# db9splitter.net
KiCad netlist of a schematic drawn in EAGLE
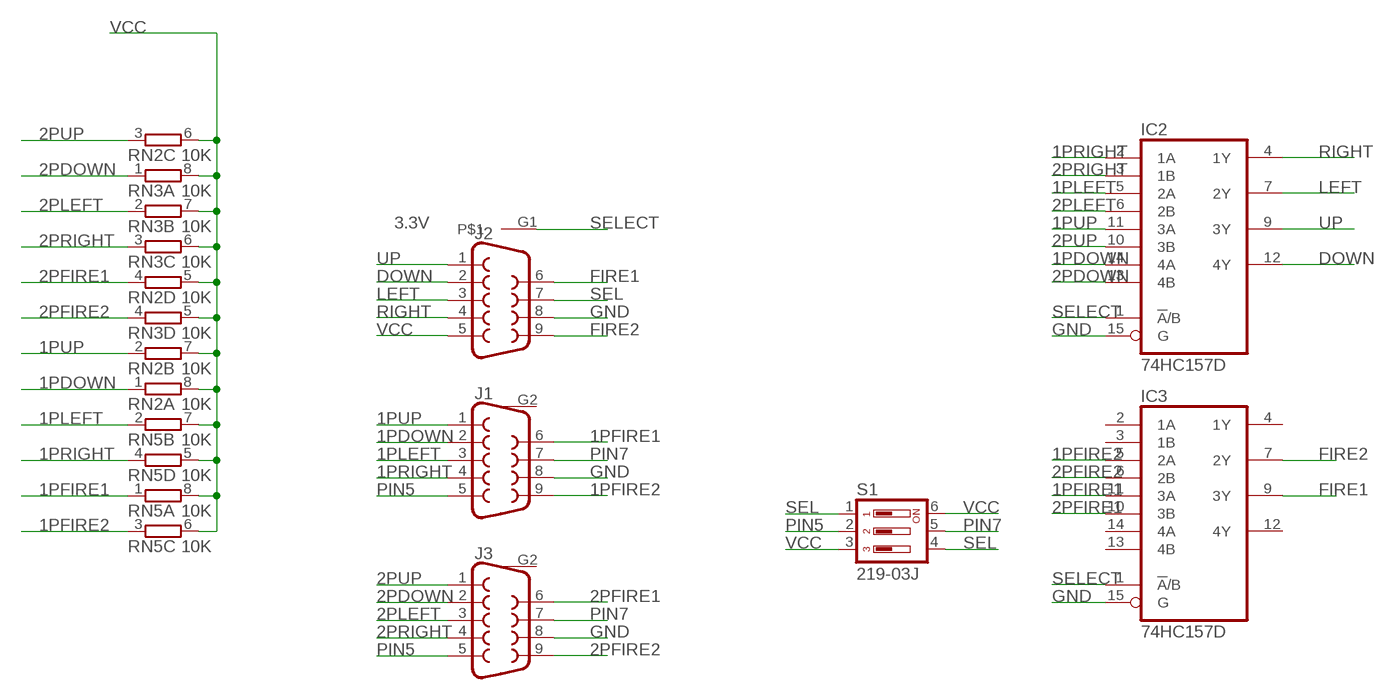
[diagram p0: schematic, sheet 1]

(export (version "E")
  (design (tool "Eeschema 10.0.6"))
  (components
    (comp (ref "IC2")
      (value "74HC157D")
      (footprint "eagle-import:SO16")
      (libsource (lib "eagle-import") (part "74157DHC"))
    )
    (comp (ref "IC3")
      (value "74HC157D")
      (footprint "eagle-import:SO16")
      (libsource (lib "eagle-import") (part "74157DHC"))
    )
    (comp (ref "J1")
      (value "SPARKFUN-CONNECTORS_DB9MALE")
      (footprint "eagle-import:SPARKFUN-CONNECTORS_DB9_MALE")
      (libsource (lib "eagle-import") (part "SPARKFUN-CONNECTORS_DB9MALE"))
    )
    (comp (ref "J2")
      (value "DB9FEMALE")
      (footprint "eagle-import:DB9")
      (libsource (lib "eagle-import") (part "DB9FEMALE"))
    )
    (comp (ref "J3")
      (value "SPARKFUN-CONNECTORS_DB9MALE")
      (footprint "eagle-import:SPARKFUN-CONNECTORS_DB9_MALE")
      (libsource (lib "eagle-import") (part "SPARKFUN-CONNECTORS_DB9MALE"))
    )
    (comp (ref "RN2")
      (value "10K")
      (footprint "eagle-import:0603-ARC")
      (libsource (lib "eagle-import") (part "4R-N0603-ARC"))
    )
    (comp (ref "RN3")
      (value "10K")
      (footprint "eagle-import:0603-ARC")
      (libsource (lib "eagle-import") (part "4R-N0603-ARC"))
    )
    (comp (ref "RN5")
      (value "10K")
      (footprint "eagle-import:0603-ARC")
      (libsource (lib "eagle-import") (part "4R-N0603-ARC"))
    )
    (comp (ref "S1")
      (value "219-03J")
      (footprint "eagle-import:CTS-219-03J")
      (libsource (lib "eagle-import") (part "219-03J"))
    )
  )
  (nets
    (net (code "1") (name "/1PDOWN") (class "Default")
      (node (ref "IC2") (pin "14") (pinfunction "4A_14") (pintype "input"))
      (node (ref "J1") (pin "2") (pinfunction "2_2") (pintype "passive"))
      (node (ref "RN2") (pin "1") (pinfunction "1_1") (pintype "passive"))
    )
    (net (code "2") (name "/1PFIRE1") (class "Default")
      (node (ref "IC3") (pin "11") (pinfunction "3A_11") (pintype "input"))
      (node (ref "J1") (pin "6") (pinfunction "6_6") (pintype "passive"))
      (node (ref "RN5") (pin "1") (pinfunction "1_1") (pintype "passive"))
    )
    (net (code "3") (name "/1PFIRE2") (class "Default")
      (node (ref "IC3") (pin "5") (pinfunction "2A_5") (pintype "input"))
      (node (ref "J1") (pin "9") (pinfunction "9_9") (pintype "passive"))
      (node (ref "RN5") (pin "3") (pinfunction "1_3") (pintype "passive"))
    )
    (net (code "4") (name "/1PLEFT") (class "Default")
      (node (ref "IC2") (pin "5") (pinfunction "2A_5") (pintype "input"))
      (node (ref "J1") (pin "3") (pinfunction "3_3") (pintype "passive"))
      (node (ref "RN5") (pin "2") (pinfunction "1_2") (pintype "passive"))
    )
    (net (code "5") (name "/1PRIGHT") (class "Default")
      (node (ref "IC2") (pin "2") (pinfunction "1A_2") (pintype "input"))
      (node (ref "J1") (pin "4") (pinfunction "4_4") (pintype "passive"))
      (node (ref "RN5") (pin "4") (pinfunction "1_4") (pintype "passive"))
    )
    (net (code "6") (name "/1PUP") (class "Default")
      (node (ref "IC2") (pin "11") (pinfunction "3A_11") (pintype "input"))
      (node (ref "J1") (pin "1") (pinfunction "1_1") (pintype "passive"))
      (node (ref "RN2") (pin "2") (pinfunction "1_2") (pintype "passive"))
    )
    (net (code "7") (name "/2PDOWN") (class "Default")
      (node (ref "IC2") (pin "13") (pinfunction "4B_13") (pintype "input"))
      (node (ref "J3") (pin "2") (pinfunction "2_2") (pintype "passive"))
      (node (ref "RN3") (pin "1") (pinfunction "1_1") (pintype "passive"))
    )
    (net (code "8") (name "/2PFIRE1") (class "Default")
      (node (ref "IC3") (pin "10") (pinfunction "3B_10") (pintype "input"))
      (node (ref "J3") (pin "6") (pinfunction "6_6") (pintype "passive"))
      (node (ref "RN2") (pin "4") (pinfunction "1_4") (pintype "passive"))
    )
    (net (code "9") (name "/2PFIRE2") (class "Default")
      (node (ref "IC3") (pin "6") (pinfunction "2B_6") (pintype "input"))
      (node (ref "J3") (pin "9") (pinfunction "9_9") (pintype "passive"))
      (node (ref "RN3") (pin "4") (pinfunction "1_4") (pintype "passive"))
    )
    (net (code "10") (name "/2PLEFT") (class "Default")
      (node (ref "IC2") (pin "6") (pinfunction "2B_6") (pintype "input"))
      (node (ref "J3") (pin "3") (pinfunction "3_3") (pintype "passive"))
      (node (ref "RN3") (pin "2") (pinfunction "1_2") (pintype "passive"))
    )
    (net (code "11") (name "/2PRIGHT") (class "Default")
      (node (ref "IC2") (pin "3") (pinfunction "1B_3") (pintype "input"))
      (node (ref "J3") (pin "4") (pinfunction "4_4") (pintype "passive"))
      (node (ref "RN3") (pin "3") (pinfunction "1_3") (pintype "passive"))
    )
    (net (code "12") (name "/2PUP") (class "Default")
      (node (ref "IC2") (pin "10") (pinfunction "3B_10") (pintype "input"))
      (node (ref "J3") (pin "1") (pinfunction "1_1") (pintype "passive"))
      (node (ref "RN2") (pin "3") (pinfunction "1_3") (pintype "passive"))
    )
    (net (code "14") (name "/DOWN") (class "Default")
      (node (ref "IC2") (pin "12") (pinfunction "4Y_12") (pintype "output"))
      (node (ref "J2") (pin "2") (pinfunction "2_2") (pintype "passive"))
    )
    (net (code "15") (name "/FIRE1") (class "Default")
      (node (ref "IC3") (pin "9") (pinfunction "3Y_9") (pintype "output"))
      (node (ref "J2") (pin "6") (pinfunction "6_6") (pintype "passive"))
    )
    (net (code "16") (name "/FIRE2") (class "Default")
      (node (ref "IC3") (pin "7") (pinfunction "2Y_7") (pintype "output"))
      (node (ref "J2") (pin "9") (pinfunction "9_9") (pintype "passive"))
    )
    (net (code "17") (name "/GND") (class "Default")
      (node (ref "IC2") (pin "15") (pinfunction "G_15") (pintype "input"))
      (node (ref "IC3") (pin "15") (pinfunction "G_15") (pintype "input"))
      (node (ref "J1") (pin "8") (pinfunction "8_8") (pintype "passive"))
      (node (ref "J2") (pin "8") (pinfunction "8_8") (pintype "passive"))
      (node (ref "J3") (pin "8") (pinfunction "8_8") (pintype "passive"))
    )
    (net (code "18") (name "/LEFT") (class "Default")
      (node (ref "IC2") (pin "7") (pinfunction "2Y_7") (pintype "output"))
      (node (ref "J2") (pin "3") (pinfunction "3_3") (pintype "passive"))
    )
    (net (code "19") (name "/PIN5") (class "Default")
      (node (ref "J1") (pin "5") (pinfunction "5_5") (pintype "passive"))
      (node (ref "J3") (pin "5") (pinfunction "5_5") (pintype "passive"))
      (node (ref "S1") (pin "2") (pinfunction "2_2") (pintype "passive"))
    )
    (net (code "20") (name "/PIN7") (class "Default")
      (node (ref "J1") (pin "7") (pinfunction "7_7") (pintype "passive"))
      (node (ref "J3") (pin "7") (pinfunction "7_7") (pintype "passive"))
      (node (ref "S1") (pin "5") (pinfunction "5_5") (pintype "passive"))
    )
    (net (code "21") (name "/RIGHT") (class "Default")
      (node (ref "IC2") (pin "4") (pinfunction "1Y_4") (pintype "output"))
      (node (ref "J2") (pin "4") (pinfunction "4_4") (pintype "passive"))
    )
    (net (code "22") (name "/SEL") (class "Default")
      (node (ref "J2") (pin "7") (pinfunction "7_7") (pintype "passive"))
      (node (ref "S1") (pin "1") (pinfunction "1_1") (pintype "passive"))
      (node (ref "S1") (pin "4") (pinfunction "4_4") (pintype "passive"))
    )
    (net (code "23") (name "/SELECT") (class "Default")
      (node (ref "IC2") (pin "1") (pinfunction "~{A}/B_1") (pintype "input"))
      (node (ref "IC3") (pin "1") (pinfunction "~{A}/B_1") (pintype "input"))
      (node (ref "J2") (pin "G1") (pinfunction "P$1_G1") (pintype "bidirectional"))
    )
    (net (code "24") (name "/UP") (class "Default")
      (node (ref "IC2") (pin "9") (pinfunction "3Y_9") (pintype "output"))
      (node (ref "J2") (pin "1") (pinfunction "1_1") (pintype "passive"))
    )
    (net (code "25") (name "/VCC") (class "Default")
      (node (ref "J2") (pin "5") (pinfunction "5_5") (pintype "passive"))
      (node (ref "RN2") (pin "5") (pinfunction "2_5") (pintype "passive"))
      (node (ref "RN2") (pin "6") (pinfunction "2_6") (pintype "passive"))
      (node (ref "RN2") (pin "7") (pinfunction "2_7") (pintype "passive"))
      (node (ref "RN2") (pin "8") (pinfunction "2_8") (pintype "passive"))
      (node (ref "RN3") (pin "5") (pinfunction "2_5") (pintype "passive"))
      (node (ref "RN3") (pin "6") (pinfunction "2_6") (pintype "passive"))
      (node (ref "RN3") (pin "7") (pinfunction "2_7") (pintype "passive"))
      (node (ref "RN3") (pin "8") (pinfunction "2_8") (pintype "passive"))
      (node (ref "RN5") (pin "5") (pinfunction "2_5") (pintype "passive"))
      (node (ref "RN5") (pin "6") (pinfunction "2_6") (pintype "passive"))
      (node (ref "RN5") (pin "7") (pinfunction "2_7") (pintype "passive"))
      (node (ref "RN5") (pin "8") (pinfunction "2_8") (pintype "passive"))
      (node (ref "S1") (pin "3") (pinfunction "3_3") (pintype "passive"))
      (node (ref "S1") (pin "6") (pinfunction "6_6") (pintype "passive"))
    )
    (net (code "26") (name "unconnected-(IC3A-1A-Pad2)") (class "Default")
      (node (ref "IC3") (pin "2") (pinfunction "1A_2") (pintype "input"))
    )
    (net (code "27") (name "unconnected-(IC3A-1B-Pad3)") (class "Default")
      (node (ref "IC3") (pin "3") (pinfunction "1B_3") (pintype "input"))
    )
    (net (code "28") (name "unconnected-(IC3A-1Y-Pad4)") (class "Default")
      (node (ref "IC3") (pin "4") (pinfunction "1Y_4") (pintype "output"))
    )
    (net (code "29") (name "unconnected-(IC3A-4A-Pad14)") (class "Default")
      (node (ref "IC3") (pin "14") (pinfunction "4A_14") (pintype "input"))
    )
    (net (code "30") (name "unconnected-(IC3A-4B-Pad13)") (class "Default")
      (node (ref "IC3") (pin "13") (pinfunction "4B_13") (pintype "input"))
    )
    (net (code "31") (name "unconnected-(IC3A-4Y-Pad12)") (class "Default")
      (node (ref "IC3") (pin "12") (pinfunction "4Y_12") (pintype "output"))
    )
    (net (code "32") (name "unconnected-(J1-10-PadG2)") (class "Default")
      (node (ref "J1") (pin "G2") (pinfunction "10_G2") (pintype "passive"))
    )
    (net (code "33") (name "unconnected-(J3-10-PadG2)") (class "Default")
      (node (ref "J3") (pin "G2") (pinfunction "10_G2") (pintype "passive"))
    )
  )
)
